# CD74HC4067_MUX_4.net
KiCad netlist of a schematic drawn in Altium Designer
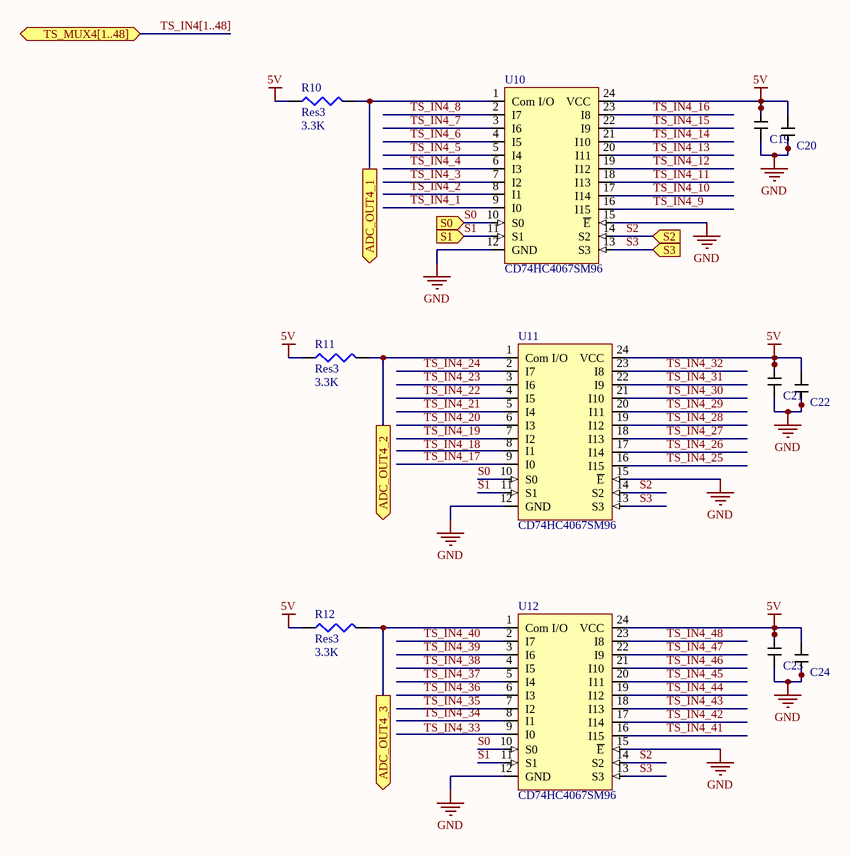
[diagram p0: CD74HC4067_MUX_4.SchDoc]

(export (version "E")
  (design (tool "Eeschema 10.0.6"))
  (components
    (comp (ref "C19")
      (value "0.1uF Cap")
      (footprint "CAPC1608X09M")
      (description "C0603C101K8GAC7867 Kemet Capacitor")
      (libsource (lib "0.1_uF_Kemet_Cap") (part "0.1uF Cap"))
    )
    (comp (ref "C20")
      (value "1uF Samsung Cap")
      (footprint "CAPC1608X09M")
      (libsource (lib "1uF_Samsung_Cap") (part "1uF Samsung Cap"))
    )
    (comp (ref "C21")
      (value "0.1uF Cap")
      (footprint "CAPC1608X09M")
      (description "C0603C101K8GAC7867 Kemet Capacitor")
      (libsource (lib "0.1_uF_Kemet_Cap") (part "0.1uF Cap"))
    )
    (comp (ref "C22")
      (value "1uF Samsung Cap")
      (footprint "CAPC1608X09M")
      (libsource (lib "1uF_Samsung_Cap") (part "1uF Samsung Cap"))
    )
    (comp (ref "C23")
      (value "0.1uF Cap")
      (footprint "CAPC1608X09M")
      (description "C0603C101K8GAC7867 Kemet Capacitor")
      (libsource (lib "0.1_uF_Kemet_Cap") (part "0.1uF Cap"))
    )
    (comp (ref "C24")
      (value "1uF Samsung Cap")
      (footprint "CAPC1608X09M")
      (libsource (lib "1uF_Samsung_Cap") (part "1uF Samsung Cap"))
    )
    (comp (ref "R10")
      (value "Res3")
      (footprint "J1-0603")
      (description "Resistor")
      (fields (field (name "ALTIUM_VALUE") "3.3K") (field (name "PUBLISHER") "Altium Limited"))
      (libsource (lib "Miscellaneous Devices") (part "Res3"))
    )
    (comp (ref "R11")
      (value "Res3")
      (footprint "J1-0603")
      (description "Resistor")
      (fields (field (name "ALTIUM_VALUE") "3.3K") (field (name "PUBLISHER") "Altium Limited"))
      (libsource (lib "Miscellaneous Devices") (part "Res3"))
    )
    (comp (ref "R12")
      (value "Res3")
      (footprint "J1-0603")
      (description "Resistor")
      (fields (field (name "ALTIUM_VALUE") "3.3K") (field (name "PUBLISHER") "Altium Limited"))
      (libsource (lib "Miscellaneous Devices") (part "Res3"))
    )
    (comp (ref "U10")
      (value "CD74HC4067SM96")
      (footprint "SOIC-24_MUX")
      (libsource (lib "TI_Mux") (part "CD74HC4067SM96"))
    )
    (comp (ref "U11")
      (value "CD74HC4067SM96")
      (footprint "SOIC-24_MUX")
      (libsource (lib "TI_Mux") (part "CD74HC4067SM96"))
    )
    (comp (ref "U12")
      (value "CD74HC4067SM96")
      (footprint "SOIC-24_MUX")
      (libsource (lib "TI_Mux") (part "CD74HC4067SM96"))
    )
  )
  (nets
    (net (code "49") (name "/ADC_OUT4_1") (class "Default")
      (node (ref "R10") (pin "2") (pinfunction "2_2") (pintype "passive"))
      (node (ref "U10") (pin "1") (pinfunction "Com_I/O_1") (pintype "bidirectional"))
    )
    (net (code "50") (name "/ADC_OUT4_2") (class "Default")
      (node (ref "R11") (pin "2") (pinfunction "2_2") (pintype "passive"))
      (node (ref "U11") (pin "1") (pinfunction "Com_I/O_1") (pintype "bidirectional"))
    )
    (net (code "51") (name "/ADC_OUT4_3") (class "Default")
      (node (ref "R12") (pin "2") (pinfunction "2_2") (pintype "passive"))
      (node (ref "U12") (pin "1") (pinfunction "Com_I/O_1") (pintype "bidirectional"))
    )
    (net (code "52") (name "/S0") (class "Default")
      (node (ref "U10") (pin "10") (pinfunction "S0_10") (pintype "input"))
      (node (ref "U11") (pin "10") (pinfunction "S0_10") (pintype "input"))
      (node (ref "U12") (pin "10") (pinfunction "S0_10") (pintype "input"))
    )
    (net (code "53") (name "/S1") (class "Default")
      (node (ref "U10") (pin "11") (pinfunction "S1_11") (pintype "input"))
      (node (ref "U11") (pin "11") (pinfunction "S1_11") (pintype "input"))
      (node (ref "U12") (pin "11") (pinfunction "S1_11") (pintype "input"))
    )
    (net (code "54") (name "/S2") (class "Default")
      (node (ref "U10") (pin "14") (pinfunction "S2_14") (pintype "input"))
      (node (ref "U11") (pin "14") (pinfunction "S2_14") (pintype "input"))
      (node (ref "U12") (pin "14") (pinfunction "S2_14") (pintype "input"))
    )
    (net (code "55") (name "/S3") (class "Default")
      (node (ref "U10") (pin "13") (pinfunction "S3_13") (pintype "input"))
      (node (ref "U11") (pin "13") (pinfunction "S3_13") (pintype "input"))
      (node (ref "U12") (pin "13") (pinfunction "S3_13") (pintype "input"))
    )
    (net (code "57") (name "/TS_IN4_1") (class "Default")
      (node (ref "U10") (pin "9") (pinfunction "I0_9") (pintype "passive"))
    )
    (net (code "58") (name "/TS_IN4_2") (class "Default")
      (node (ref "U10") (pin "8") (pinfunction "I1_8") (pintype "passive"))
    )
    (net (code "59") (name "/TS_IN4_3") (class "Default")
      (node (ref "U10") (pin "7") (pinfunction "I2_7") (pintype "passive"))
    )
    (net (code "60") (name "/TS_IN4_4") (class "Default")
      (node (ref "U10") (pin "6") (pinfunction "I3_6") (pintype "passive"))
    )
    (net (code "61") (name "/TS_IN4_5") (class "Default")
      (node (ref "U10") (pin "5") (pinfunction "I4_5") (pintype "passive"))
    )
    (net (code "62") (name "/TS_IN4_6") (class "Default")
      (node (ref "U10") (pin "4") (pinfunction "I5_4") (pintype "passive"))
    )
    (net (code "63") (name "/TS_IN4_7") (class "Default")
      (node (ref "U10") (pin "3") (pinfunction "I6_3") (pintype "passive"))
    )
    (net (code "64") (name "/TS_IN4_8") (class "Default")
      (node (ref "U10") (pin "2") (pinfunction "I7_2") (pintype "passive"))
    )
    (net (code "65") (name "/TS_IN4_9") (class "Default")
      (node (ref "U10") (pin "16") (pinfunction "I15_16") (pintype "passive"))
    )
    (net (code "66") (name "/TS_IN4_10") (class "Default")
      (node (ref "U10") (pin "17") (pinfunction "I14_17") (pintype "passive"))
    )
    (net (code "67") (name "/TS_IN4_11") (class "Default")
      (node (ref "U10") (pin "18") (pinfunction "I13_18") (pintype "passive"))
    )
    (net (code "68") (name "/TS_IN4_12") (class "Default")
      (node (ref "U10") (pin "19") (pinfunction "I12_19") (pintype "passive"))
    )
    (net (code "69") (name "/TS_IN4_13") (class "Default")
      (node (ref "U10") (pin "20") (pinfunction "I11_20") (pintype "passive"))
    )
    (net (code "70") (name "/TS_IN4_14") (class "Default")
      (node (ref "U10") (pin "21") (pinfunction "I10_21") (pintype "passive"))
    )
    (net (code "71") (name "/TS_IN4_15") (class "Default")
      (node (ref "U10") (pin "22") (pinfunction "I9_22") (pintype "passive"))
    )
    (net (code "72") (name "/TS_IN4_16") (class "Default")
      (node (ref "U10") (pin "23") (pinfunction "I8_23") (pintype "passive"))
    )
    (net (code "73") (name "/TS_IN4_17") (class "Default")
      (node (ref "U11") (pin "9") (pinfunction "I0_9") (pintype "passive"))
    )
    (net (code "75") (name "/TS_IN4_19") (class "Default")
      (node (ref "U11") (pin "7") (pinfunction "I2_7") (pintype "passive"))
    )
    (net (code "76") (name "/TS_IN4_20") (class "Default")
      (node (ref "U11") (pin "6") (pinfunction "I3_6") (pintype "passive"))
    )
    (net (code "77") (name "/TS_IN4_21") (class "Default")
      (node (ref "U11") (pin "5") (pinfunction "I4_5") (pintype "passive"))
    )
    (net (code "78") (name "/TS_IN4_22") (class "Default")
      (node (ref "U11") (pin "4") (pinfunction "I5_4") (pintype "passive"))
    )
    (net (code "79") (name "/TS_IN4_23") (class "Default")
      (node (ref "U11") (pin "3") (pinfunction "I6_3") (pintype "passive"))
    )
    (net (code "80") (name "/TS_IN4_24") (class "Default")
      (node (ref "U11") (pin "2") (pinfunction "I7_2") (pintype "passive"))
    )
    (net (code "81") (name "/TS_IN4_25") (class "Default")
      (node (ref "U11") (pin "16") (pinfunction "I15_16") (pintype "passive"))
    )
    (net (code "82") (name "/TS_IN4_26") (class "Default")
      (node (ref "U11") (pin "17") (pinfunction "I14_17") (pintype "passive"))
    )
    (net (code "83") (name "/TS_IN4_27") (class "Default")
      (node (ref "U11") (pin "18") (pinfunction "I13_18") (pintype "passive"))
    )
    (net (code "84") (name "/TS_IN4_28") (class "Default")
      (node (ref "U11") (pin "19") (pinfunction "I12_19") (pintype "passive"))
    )
    (net (code "85") (name "/TS_IN4_29") (class "Default")
      (node (ref "U11") (pin "20") (pinfunction "I11_20") (pintype "passive"))
    )
    (net (code "86") (name "/TS_IN4_30") (class "Default")
      (node (ref "U11") (pin "21") (pinfunction "I10_21") (pintype "passive"))
    )
    (net (code "87") (name "/TS_IN4_31") (class "Default")
      (node (ref "U11") (pin "22") (pinfunction "I9_22") (pintype "passive"))
    )
    (net (code "88") (name "/TS_IN4_32") (class "Default")
      (node (ref "U11") (pin "23") (pinfunction "I8_23") (pintype "passive"))
    )
    (net (code "90") (name "/TS_IN4_34") (class "Default")
      (node (ref "U12") (pin "8") (pinfunction "I1_8") (pintype "passive"))
    )
    (net (code "91") (name "/TS_IN4_35") (class "Default")
      (node (ref "U12") (pin "7") (pinfunction "I2_7") (pintype "passive"))
    )
    (net (code "92") (name "/TS_IN4_36") (class "Default")
      (node (ref "U12") (pin "6") (pinfunction "I3_6") (pintype "passive"))
    )
    (net (code "93") (name "/TS_IN4_37") (class "Default")
      (node (ref "U12") (pin "5") (pinfunction "I4_5") (pintype "passive"))
    )
    (net (code "94") (name "/TS_IN4_38") (class "Default")
      (node (ref "U12") (pin "4") (pinfunction "I5_4") (pintype "passive"))
    )
    (net (code "95") (name "/TS_IN4_39") (class "Default")
      (node (ref "U12") (pin "3") (pinfunction "I6_3") (pintype "passive"))
    )
    (net (code "96") (name "/TS_IN4_40") (class "Default")
      (node (ref "U12") (pin "2") (pinfunction "I7_2") (pintype "passive"))
    )
    (net (code "97") (name "/TS_IN4_41") (class "Default")
      (node (ref "U12") (pin "16") (pinfunction "I15_16") (pintype "passive"))
    )
    (net (code "98") (name "/TS_IN4_42") (class "Default")
      (node (ref "U12") (pin "17") (pinfunction "I14_17") (pintype "passive"))
    )
    (net (code "99") (name "/TS_IN4_43") (class "Default")
      (node (ref "U12") (pin "18") (pinfunction "I13_18") (pintype "passive"))
    )
    (net (code "100") (name "/TS_IN4_44") (class "Default")
      (node (ref "U12") (pin "19") (pinfunction "I12_19") (pintype "passive"))
    )
    (net (code "101") (name "/TS_IN4_45") (class "Default")
      (node (ref "U12") (pin "20") (pinfunction "I11_20") (pintype "passive"))
    )
    (net (code "102") (name "/TS_IN4_46") (class "Default")
      (node (ref "U12") (pin "21") (pinfunction "I10_21") (pintype "passive"))
    )
    (net (code "103") (name "/TS_IN4_47") (class "Default")
      (node (ref "U12") (pin "22") (pinfunction "I9_22") (pintype "passive"))
    )
    (net (code "104") (name "/TS_IN4_48") (class "Default")
      (node (ref "U12") (pin "23") (pinfunction "I8_23") (pintype "passive"))
    )
    (net (code "105") (name "5V") (class "Default")
      (node (ref "C19") (pin "2") (pinfunction "2_2") (pintype "passive"))
      (node (ref "C20") (pin "2") (pinfunction "2_2") (pintype "passive"))
      (node (ref "C21") (pin "2") (pinfunction "2_2") (pintype "passive"))
      (node (ref "C22") (pin "2") (pinfunction "2_2") (pintype "passive"))
      (node (ref "C23") (pin "2") (pinfunction "2_2") (pintype "passive"))
      (node (ref "C24") (pin "2") (pinfunction "2_2") (pintype "passive"))
      (node (ref "R10") (pin "1") (pinfunction "1_1") (pintype "passive"))
      (node (ref "R11") (pin "1") (pinfunction "1_1") (pintype "passive"))
      (node (ref "R12") (pin "1") (pinfunction "1_1") (pintype "passive"))
      (node (ref "U10") (pin "24") (pinfunction "VCC_24") (pintype "power_in"))
      (node (ref "U11") (pin "24") (pinfunction "VCC_24") (pintype "power_in"))
      (node (ref "U12") (pin "24") (pinfunction "VCC_24") (pintype "power_in"))
    )
    (net (code "106") (name "GND") (class "Default")
      (node (ref "C19") (pin "1") (pinfunction "1_1") (pintype "passive"))
      (node (ref "C20") (pin "1") (pinfunction "1_1") (pintype "passive"))
      (node (ref "C21") (pin "1") (pinfunction "1_1") (pintype "passive"))
      (node (ref "C22") (pin "1") (pinfunction "1_1") (pintype "passive"))
      (node (ref "C23") (pin "1") (pinfunction "1_1") (pintype "passive"))
      (node (ref "C24") (pin "1") (pinfunction "1_1") (pintype "passive"))
      (node (ref "U10") (pin "12") (pinfunction "GND_12") (pintype "power_in"))
      (node (ref "U10") (pin "15") (pinfunction "~{E}_15") (pintype "input"))
      (node (ref "U11") (pin "12") (pinfunction "GND_12") (pintype "power_in"))
      (node (ref "U11") (pin "15") (pinfunction "~{E}_15") (pintype "input"))
      (node (ref "U12") (pin "12") (pinfunction "GND_12") (pintype "power_in"))
      (node (ref "U12") (pin "15") (pinfunction "~{E}_15") (pintype "input"))
    )
    (net (code "107") (name "unconnected-(U11-I1-Pad8)") (class "Default")
      (node (ref "U11") (pin "8") (pinfunction "I1_8") (pintype "passive"))
    )
    (net (code "108") (name "unconnected-(U12-I0-Pad9)") (class "Default")
      (node (ref "U12") (pin "9") (pinfunction "I0_9") (pintype "passive"))
    )
  )
)
